# Power.net
KiCad netlist of a schematic drawn in Altium Designer
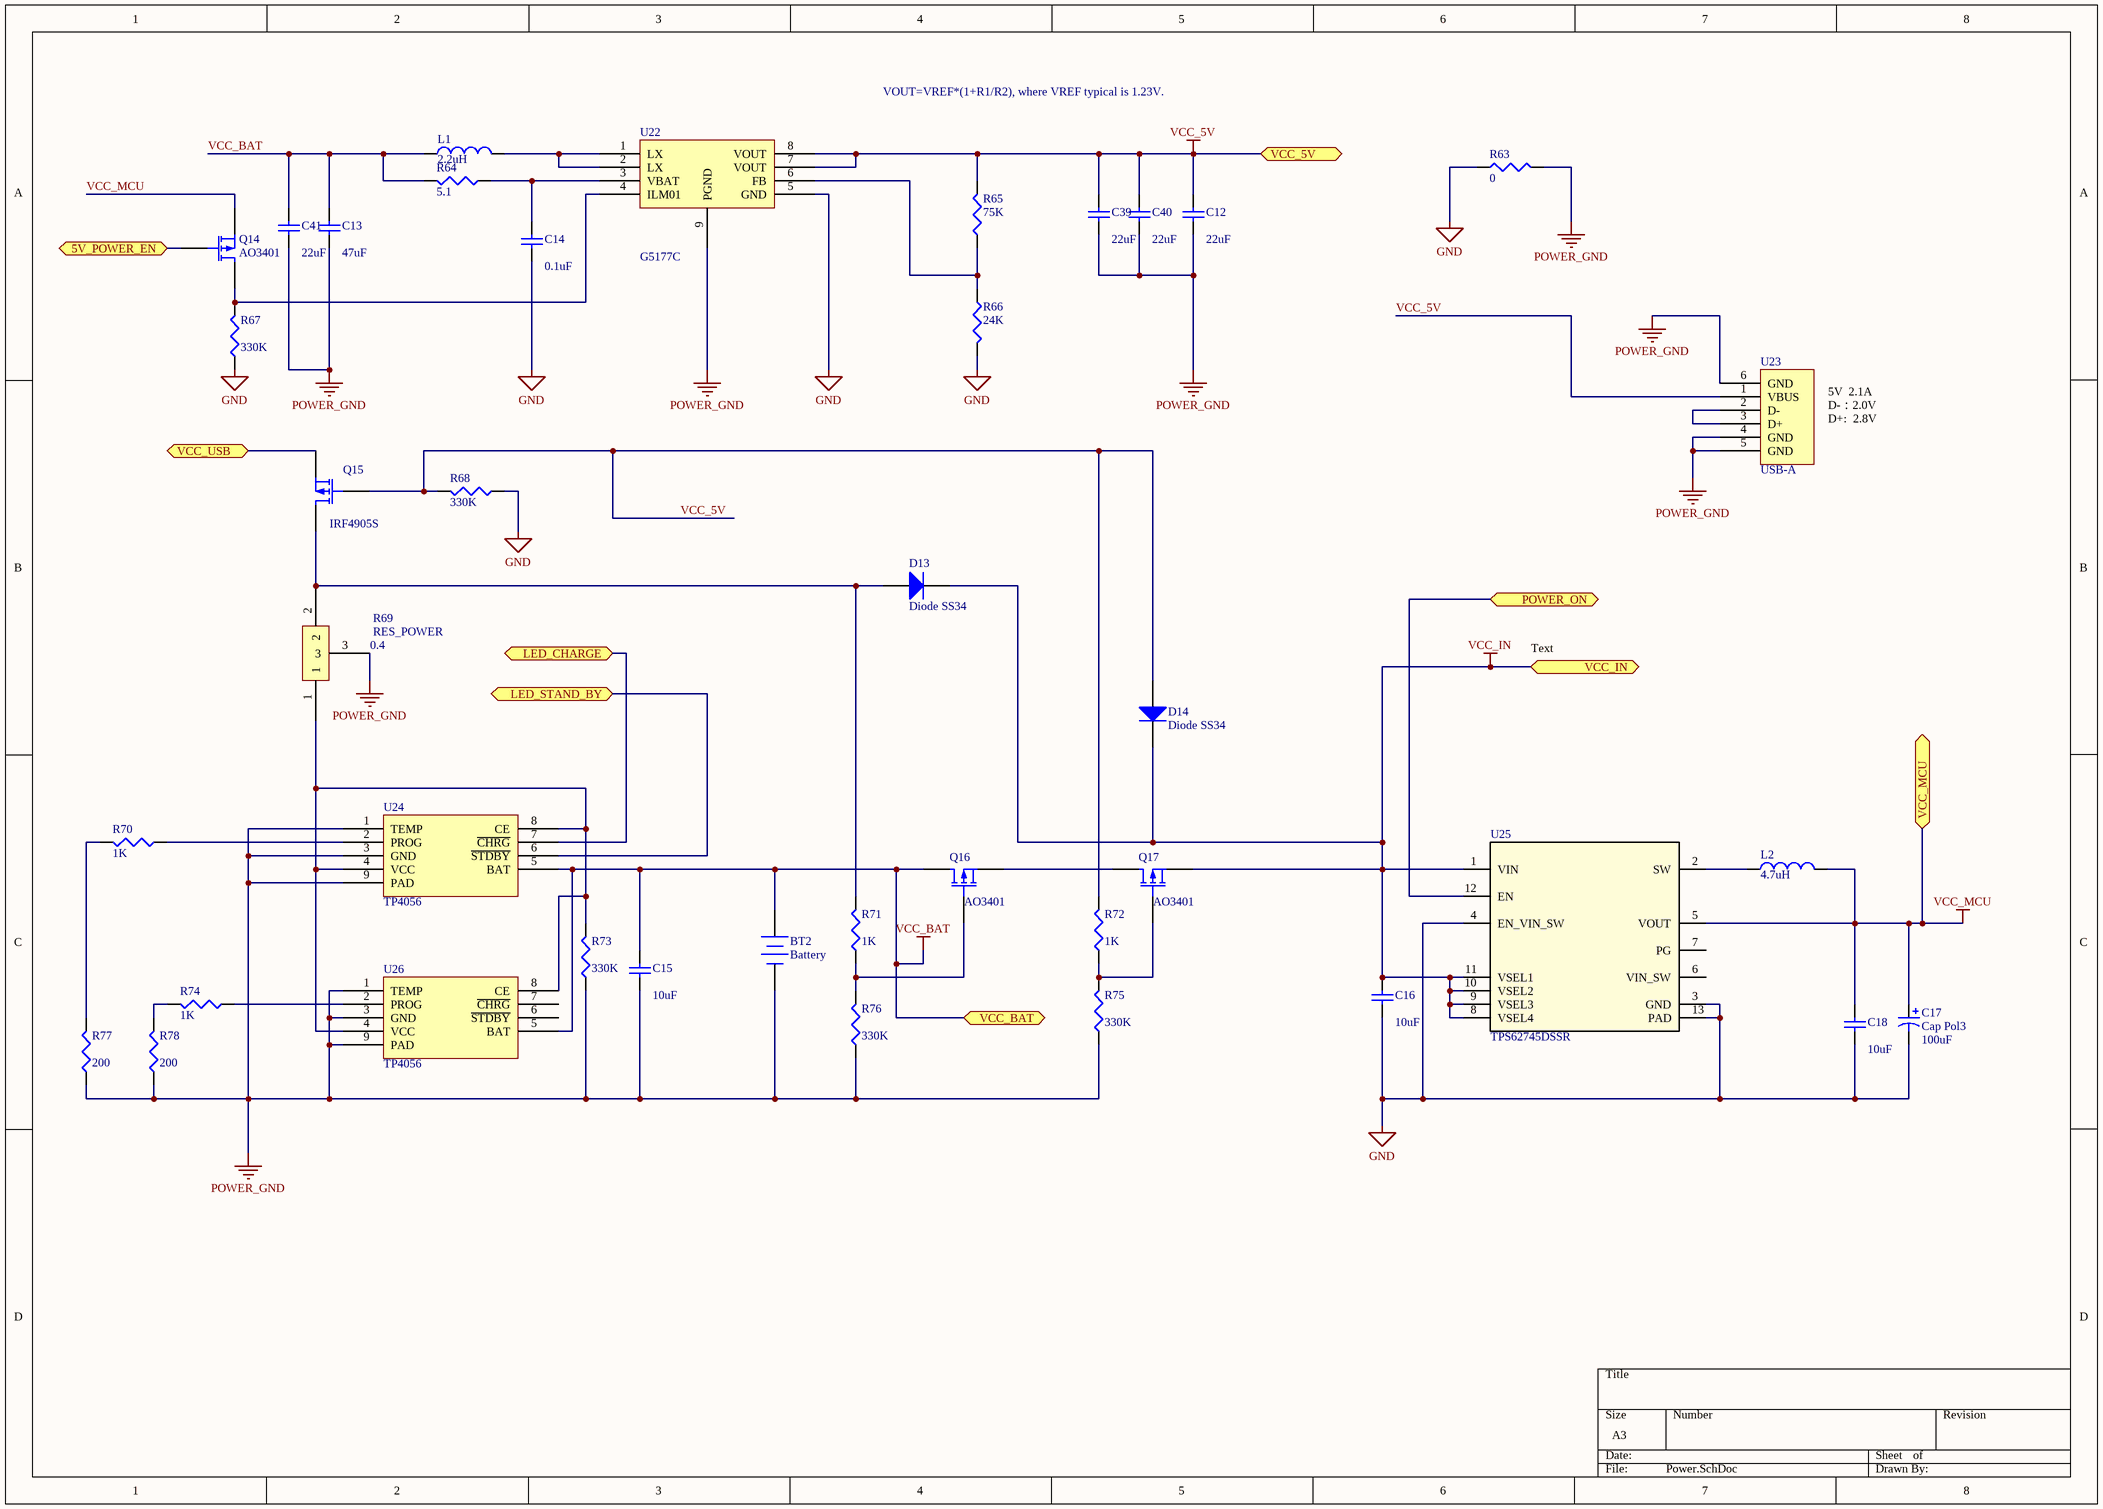
[diagram p0: Power.SchDoc]

(export (version "E")
  (design (tool "Eeschema 10.0.6"))
  (components
    (comp (ref "BT2")
      (value "Battery")
      (footprint "clock:18650X4")
      (description "Multicell Battery")
      (fields (field (name "PUBLISHER") "Altium Limited"))
      (libsource (lib "Miscellaneous Devices") (part "Battery"))
    )
    (comp (ref "C12")
      (value "22uF")
      (footprint "clock:1206")
      (description "Capacitor (Semiconductor SIM Model)")
      (fields (field (name "Comment") "Cap Semi") (field (name "PUBLISHER") "Altium Limited"))
      (libsource (lib "Miscellaneous Devices") (part "Cap Semi"))
    )
    (comp (ref "C13")
      (value "47uF")
      (footprint "clock:1210")
      (description "Capacitor (Semiconductor SIM Model)")
      (fields (field (name "Comment") "Cap Semi") (field (name "PUBLISHER") "Altium Limited"))
      (libsource (lib "Miscellaneous Devices") (part "Cap Semi"))
    )
    (comp (ref "C14")
      (value "0.1uF")
      (footprint "clock:0603")
      (description "Capacitor (Semiconductor SIM Model)")
      (fields (field (name "Comment") "Cap Semi") (field (name "PUBLISHER") "Altium Limited"))
      (libsource (lib "Miscellaneous Devices") (part "Cap Semi"))
    )
    (comp (ref "C15")
      (value "10uF")
      (footprint "clock:0603")
      (description "Capacitor (Semiconductor SIM Model)")
      (fields (field (name "Comment") "Cap Semi") (field (name "PUBLISHER") "Altium Limited"))
      (libsource (lib "Miscellaneous Devices") (part "Cap Semi"))
    )
    (comp (ref "C16")
      (value "10uF")
      (footprint "clock:0603")
      (description "Capacitor (Semiconductor SIM Model)")
      (fields (field (name "Comment") "Cap Semi") (field (name "PUBLISHER") "Altium Limited"))
      (libsource (lib "Miscellaneous Devices") (part "Cap Semi"))
    )
    (comp (ref "C17")
      (value "Cap Pol3")
      (footprint "clock:TC7343-2917")
      (description "Polarized Capacitor (Surface Mount)")
      (fields (field (name "ALTIUM_VALUE") "100uF") (field (name "PUBLISHER") "Altium Limited"))
      (libsource (lib "Miscellaneous Devices") (part "Cap Pol3"))
    )
    (comp (ref "C18")
      (value "10uF")
      (footprint "clock:0603")
      (description "Capacitor (Semiconductor SIM Model)")
      (fields (field (name "Comment") "Cap Semi") (field (name "PUBLISHER") "Altium Limited"))
      (libsource (lib "Miscellaneous Devices") (part "Cap Semi"))
    )
    (comp (ref "C39")
      (value "22uF")
      (footprint "clock:1206")
      (description "Capacitor (Semiconductor SIM Model)")
      (fields (field (name "Comment") "Cap Semi") (field (name "PUBLISHER") "Altium Limited"))
      (libsource (lib "Miscellaneous Devices") (part "Cap Semi"))
    )
    (comp (ref "C40")
      (value "22uF")
      (footprint "clock:1206")
      (description "Capacitor (Semiconductor SIM Model)")
      (fields (field (name "Comment") "Cap Semi") (field (name "PUBLISHER") "Altium Limited"))
      (libsource (lib "Miscellaneous Devices") (part "Cap Semi"))
    )
    (comp (ref "C41")
      (value "22uF")
      (footprint "clock:1206")
      (description "Capacitor (Semiconductor SIM Model)")
      (fields (field (name "Comment") "Cap Semi") (field (name "PUBLISHER") "Altium Limited"))
      (libsource (lib "Miscellaneous Devices") (part "Cap Semi"))
    )
    (comp (ref "D13")
      (value "Diode SS34")
      (footprint "clock:SMA")
      (description "1 Amp General Purpose Rectifier")
      (fields (field (name "PUBLISHER") "Altium Limited"))
      (libsource (lib "Miscellaneous Devices") (part "Diode 1N4005"))
    )
    (comp (ref "D14")
      (value "Diode SS34")
      (footprint "clock:SMA")
      (description "1 Amp General Purpose Rectifier")
      (fields (field (name "PUBLISHER") "Altium Limited"))
      (libsource (lib "Miscellaneous Devices") (part "Diode 1N4005"))
    )
    (comp (ref "L1")
      (value "2.2uH")
      (footprint "clock:WNC0630")
      (description "Inductor")
      (fields (field (name "PUBLISHER") "Altium Limited"))
      (libsource (lib "Miscellaneous Devices") (part "Inductor"))
    )
    (comp (ref "L2")
      (value "4.7uH")
      (footprint "clock:2520")
      (description "Inductor")
      (fields (field (name "PUBLISHER") "Altium Limited"))
      (libsource (lib "Miscellaneous Devices") (part "Inductor"))
    )
    (comp (ref "Q14")
      (value "AO3401")
      (footprint "clock:SOT23-3-PMOS")
      (description "P-Channel MOSFET")
      (fields (field (name "PUBLISHER") "Altium Limited"))
      (libsource (lib "Miscellaneous Devices") (part "MOSFET-P"))
    )
    (comp (ref "Q15")
      (value "IRF4905S")
      (footprint "clock:D2PAK")
      (description "P-Channel MOSFET")
      (fields (field (name "PUBLISHER") "Altium Limited"))
      (libsource (lib "Miscellaneous Devices") (part "MOSFET-P"))
    )
    (comp (ref "Q16")
      (value "AO3401")
      (footprint "clock:SOT23-3-PMOS")
      (description "P-Channel MOSFET")
      (fields (field (name "PUBLISHER") "Altium Limited"))
      (libsource (lib "Miscellaneous Devices") (part "MOSFET-P"))
    )
    (comp (ref "Q17")
      (value "AO3401")
      (footprint "clock:SOT23-3-PMOS")
      (description "P-Channel MOSFET")
      (fields (field (name "PUBLISHER") "Altium Limited"))
      (libsource (lib "Miscellaneous Devices") (part "MOSFET-P"))
    )
    (comp (ref "R63")
      (value "0")
      (footprint "clock:0603")
      (description "Resistor")
      (fields (field (name "Comment") "Res3") (field (name "PUBLISHER") "Altium Limited"))
      (libsource (lib "Miscellaneous Devices") (part "Res3"))
    )
    (comp (ref "R64")
      (value "5.1")
      (footprint "clock:0603")
      (description "Resistor")
      (fields (field (name "Comment") "Res3") (field (name "PUBLISHER") "Altium Limited"))
      (libsource (lib "Miscellaneous Devices") (part "Res3"))
    )
    (comp (ref "R65")
      (value "75K")
      (footprint "clock:0603")
      (description "Resistor")
      (fields (field (name "Comment") "Res3") (field (name "PUBLISHER") "Altium Limited"))
      (libsource (lib "Miscellaneous Devices") (part "Res3"))
    )
    (comp (ref "R66")
      (value "24K")
      (footprint "clock:0603")
      (description "Resistor")
      (fields (field (name "Comment") "Res3") (field (name "PUBLISHER") "Altium Limited"))
      (libsource (lib "Miscellaneous Devices") (part "Res3"))
    )
    (comp (ref "R67")
      (value "330K")
      (footprint "clock:0603")
      (description "Resistor")
      (fields (field (name "Comment") "Res3") (field (name "PUBLISHER") "Altium Limited"))
      (libsource (lib "Miscellaneous Devices") (part "Res3"))
    )
    (comp (ref "R68")
      (value "330K")
      (footprint "clock:0603")
      (description "Resistor")
      (fields (field (name "Comment") "Res3") (field (name "PUBLISHER") "Altium Limited"))
      (libsource (lib "Miscellaneous Devices") (part "Res3"))
    )
    (comp (ref "R69")
      (value "RES_POWER")
      (footprint "clock:RES_POWER")
      (fields (field (name "ALTIUM_VALUE") "0.4"))
      (libsource (lib "clock") (part "RES_POWER"))
    )
    (comp (ref "R70")
      (value "1K")
      (footprint "clock:0603")
      (description "Resistor")
      (fields (field (name "Comment") "Res3") (field (name "PUBLISHER") "Altium Limited"))
      (libsource (lib "Miscellaneous Devices") (part "Res3"))
    )
    (comp (ref "R71")
      (value "1K")
      (footprint "clock:0603")
      (description "Resistor")
      (fields (field (name "Comment") "Res3") (field (name "PUBLISHER") "Altium Limited"))
      (libsource (lib "Miscellaneous Devices") (part "Res3"))
    )
    (comp (ref "R72")
      (value "1K")
      (footprint "clock:0603")
      (description "Resistor")
      (fields (field (name "Comment") "Res3") (field (name "PUBLISHER") "Altium Limited"))
      (libsource (lib "Miscellaneous Devices") (part "Res3"))
    )
    (comp (ref "R73")
      (value "330K")
      (footprint "clock:0603")
      (description "Resistor")
      (fields (field (name "Comment") "Res3") (field (name "PUBLISHER") "Altium Limited"))
      (libsource (lib "Miscellaneous Devices") (part "Res3"))
    )
    (comp (ref "R74")
      (value "1K")
      (footprint "clock:0603")
      (description "Resistor")
      (fields (field (name "Comment") "Res3") (field (name "PUBLISHER") "Altium Limited"))
      (libsource (lib "Miscellaneous Devices") (part "Res3"))
    )
    (comp (ref "R75")
      (value "330K")
      (footprint "clock:0603")
      (description "Resistor")
      (fields (field (name "Comment") "Res3") (field (name "PUBLISHER") "Altium Limited"))
      (libsource (lib "Miscellaneous Devices") (part "Res3"))
    )
    (comp (ref "R76")
      (value "330K")
      (footprint "clock:0603")
      (description "Resistor")
      (fields (field (name "Comment") "Res3") (field (name "PUBLISHER") "Altium Limited"))
      (libsource (lib "Miscellaneous Devices") (part "Res3"))
    )
    (comp (ref "R77")
      (value "200")
      (footprint "clock:0603")
      (description "Resistor")
      (fields (field (name "Comment") "Res3") (field (name "PUBLISHER") "Altium Limited"))
      (libsource (lib "Miscellaneous Devices") (part "Res3"))
    )
    (comp (ref "R78")
      (value "200")
      (footprint "clock:0603")
      (description "Resistor")
      (fields (field (name "Comment") "Res3") (field (name "PUBLISHER") "Altium Limited"))
      (libsource (lib "Miscellaneous Devices") (part "Res3"))
    )
    (comp (ref "U22") (value "G5177C") (footprint "clock:SOP8-PAD") (libsource (lib "clock") (part "G5177C")))
    (comp (ref "U23")
      (value "USB-A")
      (footprint "clock:USB2.5-2H4C")
      (libsource (lib "clock") (part "USB-A"))
    )
    (comp (ref "U24") (value "TP4056") (footprint "clock:SOP8-PAD") (libsource (lib "clock") (part "TP4056")))
    (comp (ref "U25")
      (value "TPS62745DSSR")
      (footprint "DSS0012A")
      (description "Imported")
      (fields
        (field (name "ALTERNATE PARTNUMBER") "TPS62745DSST")
        (field (name "MANUFACTURER") "Texas Instruments")
      )
      (libsource (lib "clock") (part "TPS62745DSSR"))
    )
    (comp (ref "U26") (value "TP4056") (footprint "clock:SOP8-PAD") (libsource (lib "clock") (part "TP4056")))
  )
  (nets
    (net (code "1") (name "/5V_POWER_EN") (class "Default")
      (node (ref "Q14") (pin "2") (pinfunction "G_2") (pintype "passive"))
    )
    (net (code "2") (name "/LED_CHARGE") (class "Default")
      (node (ref "U24") (pin "7") (pinfunction "~{CHRG}_7") (pintype "passive"))
    )
    (net (code "3") (name "/LED_STAND_BY") (class "Default")
      (node (ref "U24") (pin "6") (pinfunction "~{STDBY}_6") (pintype "passive"))
    )
    (net (code "4") (name "/POWER_ON") (class "Default")
      (node (ref "U25") (pin "12") (pinfunction "EN_12") (pintype "passive"))
    )
    (net (code "5") (name "/VCC_USB") (class "Default")
      (node (ref "Q15") (pin "3") (pinfunction "S_3") (pintype "passive"))
    )
    (net (code "6") (name "GND") (class "Default")
      (node (ref "C14") (pin "1") (pinfunction "1_1") (pintype "passive"))
      (node (ref "C16") (pin "1") (pinfunction "1_1") (pintype "passive"))
      (node (ref "C17") (pin "2") (pinfunction "2_2") (pintype "passive"))
      (node (ref "C18") (pin "1") (pinfunction "1_1") (pintype "passive"))
      (node (ref "R63") (pin "1") (pinfunction "1_1") (pintype "passive"))
      (node (ref "R66") (pin "2") (pinfunction "2_2") (pintype "passive"))
      (node (ref "R67") (pin "1") (pinfunction "1_1") (pintype "passive"))
      (node (ref "R68") (pin "1") (pinfunction "1_1") (pintype "passive"))
      (node (ref "U22") (pin "5") (pinfunction "GND_5") (pintype "passive"))
      (node (ref "U25") (pin "13") (pinfunction "PAD_13") (pintype "passive"))
      (node (ref "U25") (pin "3") (pinfunction "GND_3") (pintype "passive"))
      (node (ref "U25") (pin "4") (pinfunction "EN_VIN_SW_4") (pintype "passive"))
    )
    (net (code "7") (name "Net-(D13-A)") (class "Default")
      (node (ref "D13") (pin "1") (pinfunction "A_1") (pintype "passive"))
      (node (ref "Q15") (pin "1") (pinfunction "D_1") (pintype "passive"))
      (node (ref "R69") (pin "2") (pinfunction "2_2") (pintype "passive"))
      (node (ref "R71") (pin "2") (pinfunction "2_2") (pintype "passive"))
    )
    (net (code "8") (name "Net-(L1-Pad2)") (class "Default")
      (node (ref "L1") (pin "2") (pinfunction "2_2") (pintype "passive"))
      (node (ref "U22") (pin "1") (pinfunction "LX_1") (pintype "passive"))
      (node (ref "U22") (pin "2") (pinfunction "LX_2") (pintype "passive"))
    )
    (net (code "9") (name "Net-(Q14-D)") (class "Default")
      (node (ref "Q14") (pin "1") (pinfunction "D_1") (pintype "passive"))
      (node (ref "R67") (pin "2") (pinfunction "2_2") (pintype "passive"))
      (node (ref "U22") (pin "4") (pinfunction "ILM01_4") (pintype "passive"))
    )
    (net (code "10") (name "Net-(Q16-G)") (class "Default")
      (node (ref "Q16") (pin "2") (pinfunction "G_2") (pintype "passive"))
      (node (ref "R71") (pin "1") (pinfunction "1_1") (pintype "passive"))
      (node (ref "R76") (pin "2") (pinfunction "2_2") (pintype "passive"))
    )
    (net (code "11") (name "Net-(Q16-S)") (class "Default")
      (node (ref "Q16") (pin "3") (pinfunction "S_3") (pintype "passive"))
      (node (ref "Q17") (pin "1") (pinfunction "D_1") (pintype "passive"))
    )
    (net (code "12") (name "Net-(Q17-G)") (class "Default")
      (node (ref "Q17") (pin "2") (pinfunction "G_2") (pintype "passive"))
      (node (ref "R72") (pin "1") (pinfunction "1_1") (pintype "passive"))
      (node (ref "R75") (pin "2") (pinfunction "2_2") (pintype "passive"))
    )
    (net (code "13") (name "Net-(R70-Pad2)") (class "Default")
      (node (ref "R70") (pin "2") (pinfunction "2_2") (pintype "passive"))
      (node (ref "R77") (pin "2") (pinfunction "2_2") (pintype "passive"))
    )
    (net (code "14") (name "Net-(R74-Pad2)") (class "Default")
      (node (ref "R74") (pin "2") (pinfunction "2_2") (pintype "passive"))
      (node (ref "R78") (pin "2") (pinfunction "2_2") (pintype "passive"))
    )
    (net (code "15") (name "Net-(U22-FB)") (class "Default")
      (node (ref "R65") (pin "1") (pinfunction "1_1") (pintype "passive"))
      (node (ref "R66") (pin "1") (pinfunction "1_1") (pintype "passive"))
      (node (ref "U22") (pin "6") (pinfunction "FB_6") (pintype "passive"))
    )
    (net (code "16") (name "Net-(U22-VBAT)") (class "Default")
      (node (ref "C14") (pin "2") (pinfunction "2_2") (pintype "passive"))
      (node (ref "R64") (pin "1") (pinfunction "1_1") (pintype "passive"))
      (node (ref "U22") (pin "3") (pinfunction "VBAT_3") (pintype "passive"))
    )
    (net (code "17") (name "Net-(U23-D+)") (class "Default")
      (node (ref "U23") (pin "2") (pinfunction "D-_2") (pintype "passive"))
      (node (ref "U23") (pin "3") (pinfunction "D+_3") (pintype "passive"))
    )
    (net (code "18") (name "Net-(U24-CE)") (class "Default")
      (node (ref "R69") (pin "1") (pinfunction "1_1") (pintype "passive"))
      (node (ref "R73") (pin "2") (pinfunction "2_2") (pintype "passive"))
      (node (ref "U24") (pin "4") (pinfunction "VCC_4") (pintype "power_in"))
      (node (ref "U24") (pin "8") (pinfunction "CE_8") (pintype "passive"))
      (node (ref "U26") (pin "4") (pinfunction "VCC_4") (pintype "power_in"))
      (node (ref "U26") (pin "8") (pinfunction "CE_8") (pintype "passive"))
    )
    (net (code "19") (name "Net-(U24-PROG)") (class "Default")
      (node (ref "R70") (pin "1") (pinfunction "1_1") (pintype "passive"))
      (node (ref "U24") (pin "2") (pinfunction "PROG_2") (pintype "passive"))
    )
    (net (code "20") (name "Net-(U25-SW)") (class "Default")
      (node (ref "L2") (pin "1") (pinfunction "1_1") (pintype "passive"))
      (node (ref "U25") (pin "2") (pinfunction "SW_2") (pintype "passive"))
    )
    (net (code "21") (name "Net-(U26-PROG)") (class "Default")
      (node (ref "R74") (pin "1") (pinfunction "1_1") (pintype "passive"))
      (node (ref "U26") (pin "2") (pinfunction "PROG_2") (pintype "passive"))
    )
    (net (code "22") (name "POWER_GND") (class "Default")
      (node (ref "BT2") (pin "2") (pinfunction "-_2") (pintype "passive"))
      (node (ref "C12") (pin "1") (pinfunction "1_1") (pintype "passive"))
      (node (ref "C13") (pin "1") (pinfunction "1_1") (pintype "passive"))
      (node (ref "C15") (pin "1") (pinfunction "1_1") (pintype "passive"))
      (node (ref "C39") (pin "1") (pinfunction "1_1") (pintype "passive"))
      (node (ref "C40") (pin "1") (pinfunction "1_1") (pintype "passive"))
      (node (ref "C41") (pin "1") (pinfunction "1_1") (pintype "passive"))
      (node (ref "R63") (pin "2") (pinfunction "2_2") (pintype "passive"))
      (node (ref "R69") (pin "3") (pinfunction "3_3") (pintype "passive"))
      (node (ref "R73") (pin "1") (pinfunction "1_1") (pintype "passive"))
      (node (ref "R75") (pin "1") (pinfunction "1_1") (pintype "passive"))
      (node (ref "R76") (pin "1") (pinfunction "1_1") (pintype "passive"))
      (node (ref "R77") (pin "1") (pinfunction "1_1") (pintype "passive"))
      (node (ref "R78") (pin "1") (pinfunction "1_1") (pintype "passive"))
      (node (ref "U22") (pin "9") (pinfunction "PGND_9") (pintype "passive"))
      (node (ref "U23") (pin "4") (pinfunction "GND_4") (pintype "passive"))
      (node (ref "U23") (pin "5") (pinfunction "GND_5") (pintype "passive"))
      (node (ref "U23") (pin "6") (pinfunction "GND_6") (pintype "passive"))
      (node (ref "U24") (pin "1") (pinfunction "TEMP_1") (pintype "passive"))
      (node (ref "U24") (pin "3") (pinfunction "GND_3") (pintype "passive"))
      (node (ref "U24") (pin "9") (pinfunction "PAD_9") (pintype "passive"))
      (node (ref "U26") (pin "1") (pinfunction "TEMP_1") (pintype "passive"))
      (node (ref "U26") (pin "3") (pinfunction "GND_3") (pintype "passive"))
      (node (ref "U26") (pin "9") (pinfunction "PAD_9") (pintype "passive"))
    )
    (net (code "23") (name "VCC_5V") (class "Default")
      (node (ref "C12") (pin "2") (pinfunction "2_2") (pintype "passive"))
      (node (ref "C39") (pin "2") (pinfunction "2_2") (pintype "passive"))
      (node (ref "C40") (pin "2") (pinfunction "2_2") (pintype "passive"))
      (node (ref "D14") (pin "1") (pinfunction "A_1") (pintype "passive"))
      (node (ref "Q15") (pin "2") (pinfunction "G_2") (pintype "passive"))
      (node (ref "R65") (pin "2") (pinfunction "2_2") (pintype "passive"))
      (node (ref "R68") (pin "2") (pinfunction "2_2") (pintype "passive"))
      (node (ref "R72") (pin "2") (pinfunction "2_2") (pintype "passive"))
      (node (ref "U22") (pin "7") (pinfunction "VOUT_7") (pintype "passive"))
      (node (ref "U22") (pin "8") (pinfunction "VOUT_8") (pintype "passive"))
      (node (ref "U23") (pin "1") (pinfunction "VBUS_1") (pintype "passive"))
    )
    (net (code "24") (name "VCC_BAT") (class "Default")
      (node (ref "BT2") (pin "1") (pinfunction "+_1") (pintype "passive"))
      (node (ref "C13") (pin "2") (pinfunction "2_2") (pintype "passive"))
      (node (ref "C15") (pin "2") (pinfunction "2_2") (pintype "passive"))
      (node (ref "C41") (pin "2") (pinfunction "2_2") (pintype "passive"))
      (node (ref "L1") (pin "1") (pinfunction "1_1") (pintype "passive"))
      (node (ref "Q16") (pin "1") (pinfunction "D_1") (pintype "passive"))
      (node (ref "R64") (pin "2") (pinfunction "2_2") (pintype "passive"))
      (node (ref "U24") (pin "5") (pinfunction "BAT_5") (pintype "passive"))
      (node (ref "U26") (pin "5") (pinfunction "BAT_5") (pintype "passive"))
    )
    (net (code "25") (name "VCC_IN") (class "Default")
      (node (ref "C16") (pin "2") (pinfunction "2_2") (pintype "passive"))
      (node (ref "D13") (pin "2") (pinfunction "K_2") (pintype "passive"))
      (node (ref "D14") (pin "2") (pinfunction "K_2") (pintype "passive"))
      (node (ref "Q17") (pin "3") (pinfunction "S_3") (pintype "passive"))
      (node (ref "U25") (pin "1") (pinfunction "VIN_1") (pintype "passive"))
      (node (ref "U25") (pin "10") (pinfunction "VSEL2_10") (pintype "passive"))
      (node (ref "U25") (pin "11") (pinfunction "VSEL1_11") (pintype "passive"))
      (node (ref "U25") (pin "8") (pinfunction "VSEL4_8") (pintype "passive"))
      (node (ref "U25") (pin "9") (pinfunction "VSEL3_9") (pintype "passive"))
    )
    (net (code "26") (name "VCC_MCU") (class "Default")
      (node (ref "C17") (pin "1") (pinfunction "1_1") (pintype "passive"))
      (node (ref "C18") (pin "2") (pinfunction "2_2") (pintype "passive"))
      (node (ref "L2") (pin "2") (pinfunction "2_2") (pintype "passive"))
      (node (ref "Q14") (pin "3") (pinfunction "S_3") (pintype "passive"))
      (node (ref "U25") (pin "5") (pinfunction "VOUT_5") (pintype "passive"))
    )
    (net (code "27") (name "unconnected-(U25-PG-Pad7)") (class "Default")
      (node (ref "U25") (pin "7") (pinfunction "PG_7") (pintype "passive"))
    )
    (net (code "28") (name "unconnected-(U25-VIN_SW-Pad6)") (class "Default")
      (node (ref "U25") (pin "6") (pinfunction "VIN_SW_6") (pintype "passive"))
    )
    (net (code "29") (name "unconnected-(U26-~{CHRG}-Pad7)") (class "Default")
      (node (ref "U26") (pin "7") (pinfunction "~{CHRG}_7") (pintype "passive"))
    )
    (net (code "30") (name "unconnected-(U26-~{STDBY}-Pad6)") (class "Default")
      (node (ref "U26") (pin "6") (pinfunction "~{STDBY}_6") (pintype "passive"))
    )
  )
)
